# Radio.net
KiCad netlist of a schematic drawn in Altium Designer
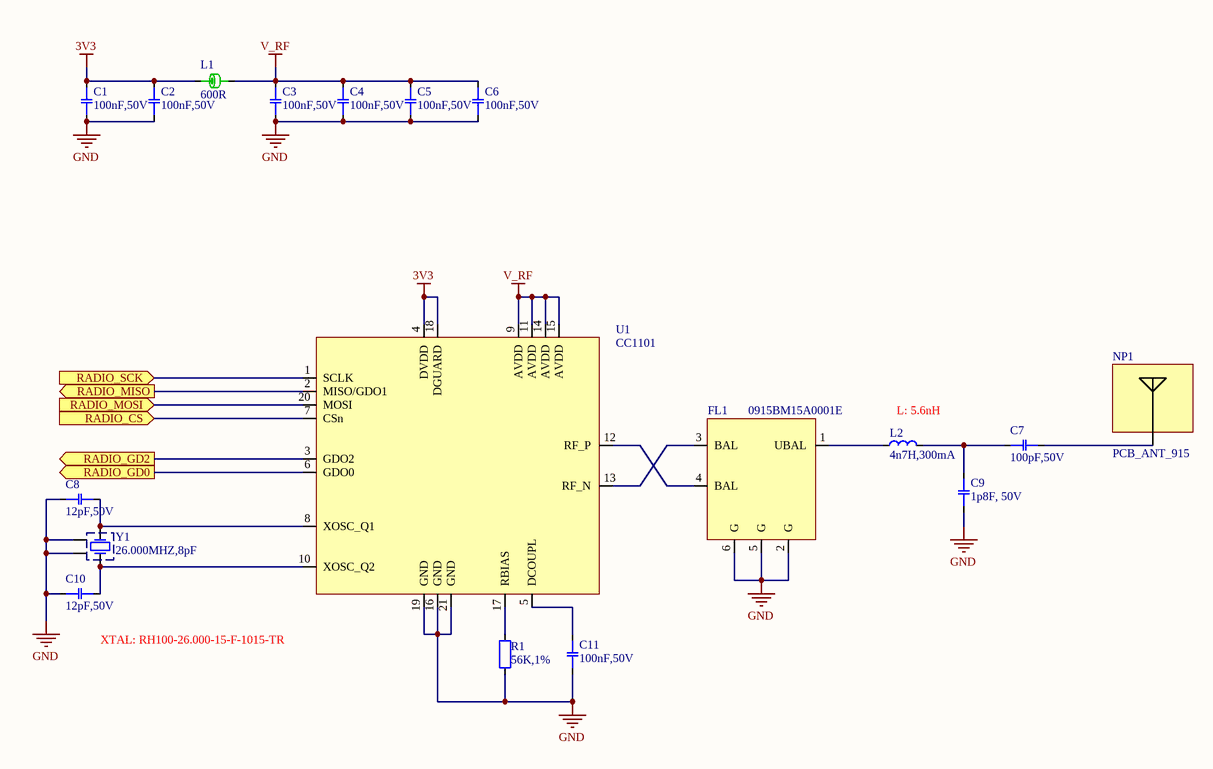
[diagram p0: Radio.SchDoc]

(export (version "E")
  (design (tool "Eeschema 10.0.6"))
  (components
    (comp (ref "C1")
      (value "100nF,50V")
      (footprint "CAPC1005X05N_0402")
      (description "CAP CER 0.1UF 50V X7R 0402")
      (fields (field (name "MANUFACTURER") "Taiyo Yuden") (field (name "TOLERANCE") "10%"))
      (libsource (lib "library") (part "CAP-NP_1"))
    )
    (comp (ref "C2")
      (value "100nF,50V")
      (footprint "CAPC1005X05N_0402")
      (description "CAP CER 0.1UF 50V X7R 0402")
      (fields (field (name "MANUFACTURER") "Taiyo Yuden") (field (name "TOLERANCE") "10%"))
      (libsource (lib "library") (part "CAP-NP_1"))
    )
    (comp (ref "C3")
      (value "100nF,50V")
      (footprint "CAPC1005X05N_0402")
      (description "CAP CER 0.1UF 50V X7R 0402")
      (fields (field (name "MANUFACTURER") "Taiyo Yuden") (field (name "TOLERANCE") "10%"))
      (libsource (lib "library") (part "CAP-NP_1"))
    )
    (comp (ref "C4")
      (value "100nF,50V")
      (footprint "CAPC1005X05N_0402")
      (description "CAP CER 0.1UF 50V X7R 0402")
      (fields (field (name "MANUFACTURER") "Taiyo Yuden") (field (name "TOLERANCE") "10%"))
      (libsource (lib "library") (part "CAP-NP_1"))
    )
    (comp (ref "C5")
      (value "100nF,50V")
      (footprint "CAPC1005X05N_0402")
      (description "CAP CER 0.1UF 50V X7R 0402")
      (fields (field (name "MANUFACTURER") "Taiyo Yuden") (field (name "TOLERANCE") "10%"))
      (libsource (lib "library") (part "CAP-NP_1"))
    )
    (comp (ref "C6")
      (value "100nF,50V")
      (footprint "CAPC1005X05N_0402")
      (description "CAP CER 0.1UF 50V X7R 0402")
      (fields (field (name "MANUFACTURER") "Taiyo Yuden") (field (name "TOLERANCE") "10%"))
      (libsource (lib "library") (part "CAP-NP_1"))
    )
    (comp (ref "C7")
      (value "100pF,50V")
      (footprint "CAPC1005X05N_0402")
      (description "CAP CER 100PF 50V 5% NP0 0402")
      (fields
        (field (name "MANUFACTURER") "Murata Electronics North America")
        (field (name "TOLERANCE") "5%")
      )
      (libsource (lib "library") (part "CAP-NP_1"))
    )
    (comp (ref "C8")
      (value "12pF,50V")
      (footprint "CAPC1005X05N_0402")
      (description "CAP CER 12PF 50V 5% NP0 0402")
      (fields
        (field (name "MANUFACTURER") "Murata Electronics North America")
        (field (name "TOLERANCE") "5%")
      )
      (libsource (lib "library") (part "CAP-NP_1"))
    )
    (comp (ref "C9")
      (value "1p8F, 50V")
      (footprint "CAPC1005X05N_0402")
      (description "CAP CER 1.8PF 50V C0G/NP0 0402")
      (fields
        (field (name "MANUFACTURER") "Murata Electronics North America")
        (field (name "TOLERANCE") "±0.1pF")
      )
      (libsource (lib "library") (part "CAP-NP_1"))
    )
    (comp (ref "C10")
      (value "12pF,50V")
      (footprint "CAPC1005X05N_0402")
      (description "CAP CER 12PF 50V 5% NP0 0402")
      (fields
        (field (name "MANUFACTURER") "Murata Electronics North America")
        (field (name "TOLERANCE") "5%")
      )
      (libsource (lib "library") (part "CAP-NP_1"))
    )
    (comp (ref "C11")
      (value "100nF,50V")
      (footprint "CAPC1005X05N_0402")
      (description "CAP CER 0.1UF 50V X7R 0402")
      (fields (field (name "MANUFACTURER") "Taiyo Yuden") (field (name "TOLERANCE") "10%"))
      (libsource (lib "library") (part "CAP-NP_1"))
    )
    (comp (ref "FL1")
      (value "0915BM15A0001E")
      (footprint "FLTR65P200X125-6N_0805")
      (description "BALUN 902MHZ-928MHZ 0805")
      (fields (field (name "MANUFACTURER") "Johanson Technology Inc"))
      (libsource (lib "library") (part "____BM15A0001E"))
    )
    (comp (ref "L1")
      (value "600R")
      (footprint "INDC1608X10N_0603")
      (description "FERRITE BEAD 600 OHM 0603 1LN")
      (fields
        (field (name "MANUFACTURER") "Wurth Electronics Inc")
        (field (name "MANUFACTURER PART NUMBER") "742792651")
      )
      (libsource (lib "library") (part "FERRITE"))
    )
    (comp (ref "L2")
      (value "4n7H,300mA")
      (footprint "INDC1005X04N_0402")
      (description "INDUCTOR 4.7NH 300MA 0402")
      (fields
        (field (name "MANUFACTURER") "Murata Electronics North America")
        (field (name "MANUFACTURER PART NUMBER") "LQG15HS4N7S02D")
      )
      (libsource (lib "library") (part "INDUCTOR_1"))
    )
    (comp (ref "NP1")
      (value "PCB_ANT_915")
      (footprint "ANT_PCB_915")
      (libsource (lib "Common") (part "PCB_ANT_915"))
    )
    (comp (ref "R1")
      (value "56K,1%")
      (footprint "RESC1005X04N_0402")
      (description "RES 56.0K OHM 1/16W 1% 0402 SMD")
      (fields (field (name "MANUFACTURER") "Yageo") (field (name "POWER") "0.063W"))
      (libsource (lib "library") (part "RESISTOR_1"))
    )
    (comp (ref "U1")
      (value "CC1101")
      (footprint "QFN50P400X400X75-20N_20QFN")
      (description "IC RF TXRX ISM<1GHZ 20VFQFN")
      (fields
        (field (name "MANUFACTURER") "Texas Instruments")
        (field (name "MANUFACTURER PART NUMBER") "CC1101RGPR")
      )
      (libsource (lib "library") (part "CC1101"))
    )
    (comp (ref "Y1")
      (value "26.000MHZ,8pF")
      (footprint "XTAL_NX3225SA")
      (description "CRYSTAL 26MHZ 8PF SMD")
      (fields
        (field (name "MANUFACTURER") "NDK")
        (field (name "MANUFACTURER PART NUMBER") "NX3225SA-26.000000MHZ-STD-CSR-1")
      )
      (libsource (lib "library") (part "XTAL_2"))
    )
  )
  (nets
    (net (code "1") (name "/RADIO_CS") (class "Default")
      (node (ref "U1") (pin "7") (pinfunction "CSn_7") (pintype "passive"))
    )
    (net (code "2") (name "/RADIO_GD0") (class "Default")
      (node (ref "U1") (pin "6") (pinfunction "GDO0_6") (pintype "passive"))
    )
    (net (code "3") (name "/RADIO_GD2") (class "Default")
      (node (ref "U1") (pin "3") (pinfunction "GDO2_3") (pintype "passive"))
    )
    (net (code "4") (name "/RADIO_MISO") (class "Default")
      (node (ref "U1") (pin "2") (pinfunction "MISO/GDO1_2") (pintype "passive"))
    )
    (net (code "5") (name "/RADIO_MOSI") (class "Default")
      (node (ref "U1") (pin "20") (pinfunction "MOSI_20") (pintype "passive"))
    )
    (net (code "6") (name "/RADIO_SCK") (class "Default")
      (node (ref "U1") (pin "1") (pinfunction "SCLK_1") (pintype "passive"))
    )
    (net (code "7") (name "3V3") (class "Default")
      (node (ref "C1") (pin "2") (pinfunction "2_2") (pintype "passive"))
      (node (ref "C2") (pin "2") (pinfunction "2_2") (pintype "passive"))
      (node (ref "L1") (pin "1") (pintype "passive"))
      (node (ref "U1") (pin "18") (pinfunction "DGUARD_18") (pintype "passive"))
      (node (ref "U1") (pin "4") (pinfunction "DVDD_4") (pintype "passive"))
    )
    (net (code "8") (name "GND") (class "Default")
      (node (ref "C1") (pin "1") (pinfunction "1_1") (pintype "passive"))
      (node (ref "C10") (pin "1") (pinfunction "1_1") (pintype "passive"))
      (node (ref "C11") (pin "1") (pinfunction "1_1") (pintype "passive"))
      (node (ref "C2") (pin "1") (pinfunction "1_1") (pintype "passive"))
      (node (ref "C3") (pin "1") (pinfunction "1_1") (pintype "passive"))
      (node (ref "C4") (pin "1") (pinfunction "1_1") (pintype "passive"))
      (node (ref "C5") (pin "1") (pinfunction "1_1") (pintype "passive"))
      (node (ref "C6") (pin "1") (pinfunction "1_1") (pintype "passive"))
      (node (ref "C8") (pin "1") (pinfunction "1_1") (pintype "passive"))
      (node (ref "C9") (pin "1") (pinfunction "1_1") (pintype "passive"))
      (node (ref "FL1") (pin "2") (pinfunction "G_2") (pintype "passive"))
      (node (ref "FL1") (pin "5") (pinfunction "G_5") (pintype "passive"))
      (node (ref "FL1") (pin "6") (pinfunction "G_6") (pintype "passive"))
      (node (ref "R1") (pin "1") (pinfunction "1_1") (pintype "passive"))
      (node (ref "U1") (pin "16") (pinfunction "GND_16") (pintype "passive"))
      (node (ref "U1") (pin "19") (pinfunction "GND_19") (pintype "passive"))
      (node (ref "U1") (pin "21") (pinfunction "GND_21") (pintype "passive"))
      (node (ref "Y1") (pin "2") (pinfunction "2_2") (pintype "passive"))
      (node (ref "Y1") (pin "4") (pinfunction "4_4") (pintype "passive"))
    )
    (net (code "9") (name "Net-(C7-Pad1)") (class "Default")
      (node (ref "C7") (pin "1") (pinfunction "1_1") (pintype "passive"))
      (node (ref "C9") (pin "2") (pinfunction "2_2") (pintype "passive"))
      (node (ref "L2") (pin "2") (pinfunction "2_2") (pintype "passive"))
    )
    (net (code "10") (name "Net-(FL1-UBAL)") (class "Default")
      (node (ref "FL1") (pin "1") (pinfunction "UBAL_1") (pintype "passive"))
      (node (ref "L2") (pin "1") (pinfunction "1_1") (pintype "passive"))
    )
    (net (code "11") (name "Net-(NP1-ANT)") (class "Default")
      (node (ref "C7") (pin "2") (pinfunction "2_2") (pintype "passive"))
      (node (ref "NP1") (pin "1") (pinfunction "ANT_1") (pintype "passive"))
    )
    (net (code "12") (name "Net-(U1-DCOUPL)") (class "Default")
      (node (ref "C11") (pin "2") (pinfunction "2_2") (pintype "passive"))
      (node (ref "U1") (pin "5") (pinfunction "DCOUPL_5") (pintype "passive"))
    )
    (net (code "13") (name "Net-(U1-RBIAS)") (class "Default")
      (node (ref "R1") (pin "2") (pinfunction "2_2") (pintype "passive"))
      (node (ref "U1") (pin "17") (pinfunction "RBIAS_17") (pintype "passive"))
    )
    (net (code "14") (name "Net-(U1-RF_N)") (class "Default")
      (node (ref "FL1") (pin "3") (pinfunction "BAL_3") (pintype "passive"))
      (node (ref "U1") (pin "13") (pinfunction "RF_N_13") (pintype "passive"))
    )
    (net (code "15") (name "Net-(U1-RF_P)") (class "Default")
      (node (ref "FL1") (pin "4") (pinfunction "BAL_4") (pintype "passive"))
      (node (ref "U1") (pin "12") (pinfunction "RF_P_12") (pintype "passive"))
    )
    (net (code "16") (name "Net-(U1-XOSC_Q1)") (class "Default")
      (node (ref "C8") (pin "2") (pinfunction "2_2") (pintype "passive"))
      (node (ref "U1") (pin "8") (pinfunction "XOSC_Q1_8") (pintype "passive"))
      (node (ref "Y1") (pin "1") (pinfunction "1_1") (pintype "passive"))
    )
    (net (code "17") (name "Net-(U1-XOSC_Q2)") (class "Default")
      (node (ref "C10") (pin "2") (pinfunction "2_2") (pintype "passive"))
      (node (ref "U1") (pin "10") (pinfunction "XOSC_Q2_10") (pintype "passive"))
      (node (ref "Y1") (pin "3") (pinfunction "3_3") (pintype "passive"))
    )
    (net (code "18") (name "V_RF") (class "Default")
      (node (ref "C3") (pin "2") (pinfunction "2_2") (pintype "passive"))
      (node (ref "C4") (pin "2") (pinfunction "2_2") (pintype "passive"))
      (node (ref "C5") (pin "2") (pinfunction "2_2") (pintype "passive"))
      (node (ref "C6") (pin "2") (pinfunction "2_2") (pintype "passive"))
      (node (ref "L1") (pin "2") (pintype "passive"))
      (node (ref "U1") (pin "11") (pinfunction "AVDD_11") (pintype "passive"))
      (node (ref "U1") (pin "14") (pinfunction "AVDD_14") (pintype "passive"))
      (node (ref "U1") (pin "15") (pinfunction "AVDD_15") (pintype "passive"))
      (node (ref "U1") (pin "9") (pinfunction "AVDD_9") (pintype "passive"))
    )
  )
)
